# LEDFB.net
KiCad netlist of a schematic drawn in EAGLE
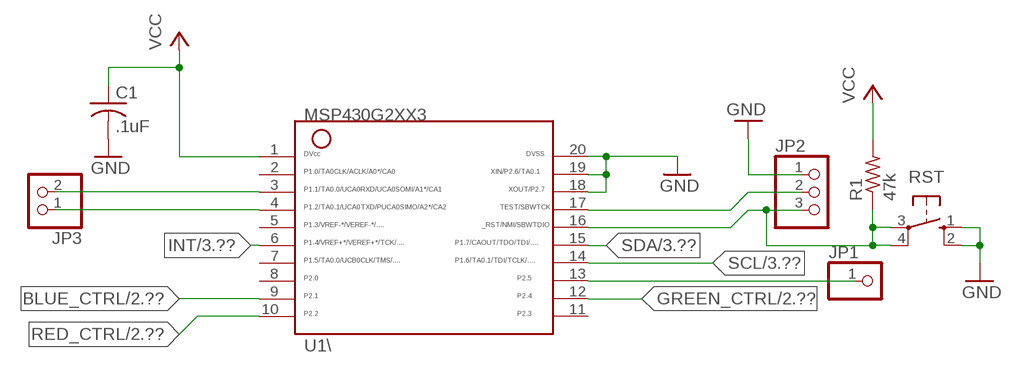
[diagram p0: schematic, sheet 1]
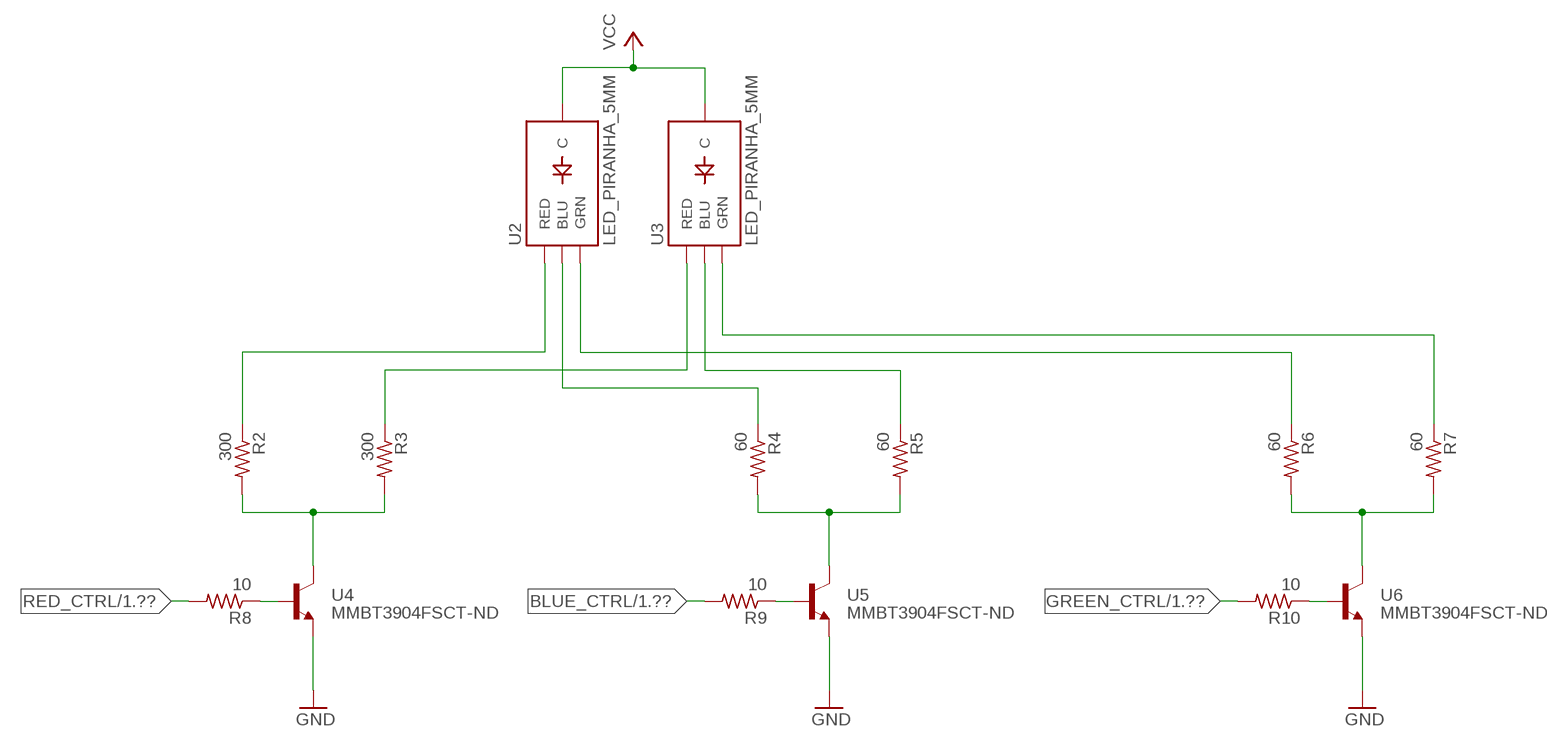
[diagram p1: schematic, sheet 2]
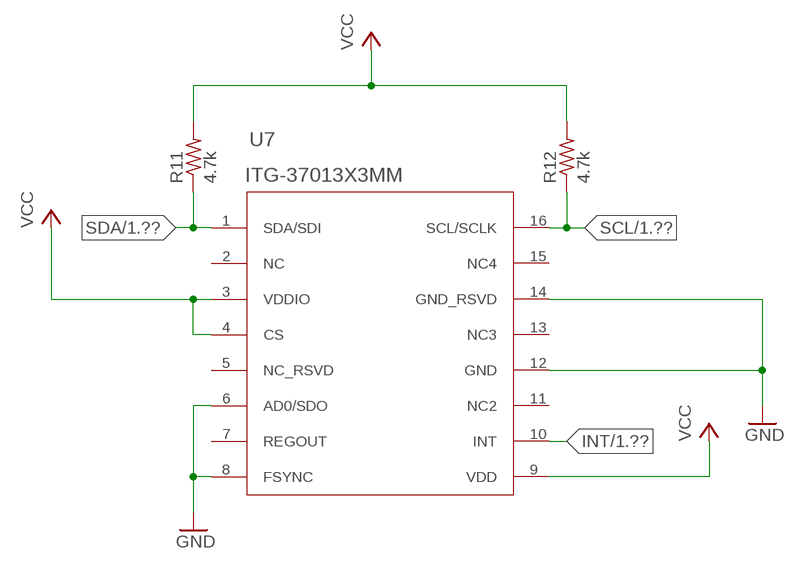
[diagram p2: schematic, sheet 3]
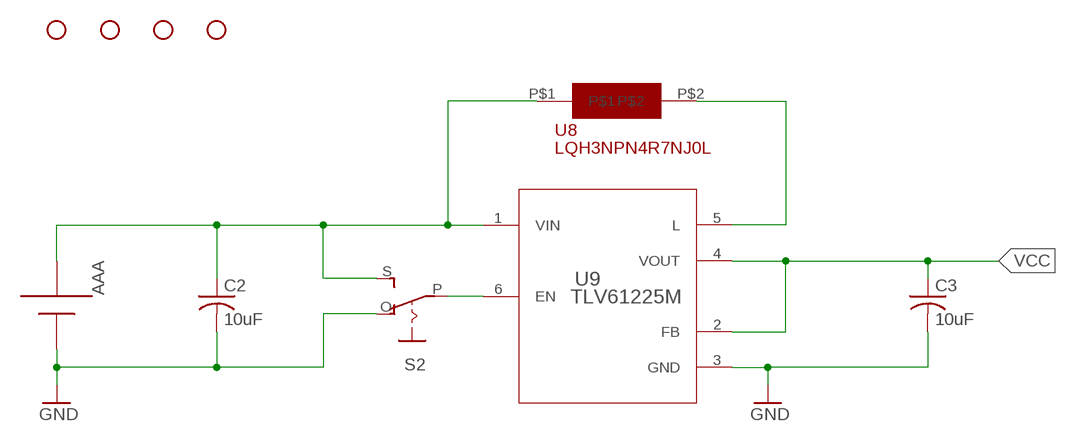
[diagram p3: schematic, sheet 4]

(export (version "E")
  (design (tool "Eeschema 10.0.6"))
  (components
    (comp (ref "C1")
      (value ".1uF")
      (footprint "eagle-import:C0805")
      (libsource (lib "eagle-import") (part "C-USC0805"))
    )
    (comp (ref "JP1")
      (value "PINHD-1X1")
      (footprint "eagle-import:1X01")
      (libsource (lib "eagle-import") (part "PINHD-1X1"))
    )
    (comp (ref "JP2")
      (value "PINHD-1X3")
      (footprint "eagle-import:1X03")
      (libsource (lib "eagle-import") (part "PINHD-1X3"))
    )
    (comp (ref "JP3")
      (value "PINHD-1X2")
      (footprint "eagle-import:1X02")
      (libsource (lib "eagle-import") (part "PINHD-1X2"))
    )
    (comp (ref "R1")
      (value "47k")
      (footprint "eagle-import:R0805")
      (libsource (lib "eagle-import") (part "R-US_R0805"))
    )
    (comp (ref "RST")
      (value "10-XX")
      (footprint "eagle-import:B3F-10XX")
      (fields (field (name "MPN") "B3F-1000"))
      (libsource (lib "eagle-import") (part "10-XX"))
    )
    (comp (ref "U1\\")
      (value "G2XX3---PW20")
      (footprint "eagle-import:PW20")
      (libsource (lib "eagle-import") (part "G2XX3---PW20"))
    )
    (comp (ref "R2")
      (value "300")
      (footprint "eagle-import:R0805")
      (libsource (lib "eagle-import") (part "R-US_R0805"))
    )
    (comp (ref "R3")
      (value "300")
      (footprint "eagle-import:R0805")
      (libsource (lib "eagle-import") (part "R-US_R0805"))
    )
    (comp (ref "R4")
      (value "60")
      (footprint "eagle-import:R0805")
      (libsource (lib "eagle-import") (part "R-US_R0805"))
    )
    (comp (ref "R5")
      (value "60")
      (footprint "eagle-import:R0805")
      (libsource (lib "eagle-import") (part "R-US_R0805"))
    )
    (comp (ref "R6")
      (value "60")
      (footprint "eagle-import:R0805")
      (libsource (lib "eagle-import") (part "R-US_R0805"))
    )
    (comp (ref "R7")
      (value "60")
      (footprint "eagle-import:R0805")
      (libsource (lib "eagle-import") (part "R-US_R0805"))
    )
    (comp (ref "R8")
      (value "10")
      (footprint "eagle-import:R0805")
      (libsource (lib "eagle-import") (part "R-US_R0805"))
    )
    (comp (ref "R9")
      (value "10")
      (footprint "eagle-import:R0805")
      (libsource (lib "eagle-import") (part "R-US_R0805"))
    )
    (comp (ref "R10")
      (value "10")
      (footprint "eagle-import:R0805")
      (libsource (lib "eagle-import") (part "R-US_R0805"))
    )
    (comp (ref "U2")
      (value "LED_PIRANHA_5MM")
      (footprint "eagle-import:LED_PIRANHA_5MM")
      (libsource (lib "eagle-import") (part "LED_PIRANHA_5MM"))
    )
    (comp (ref "U3")
      (value "LED_PIRANHA_5MM")
      (footprint "eagle-import:LED_PIRANHA_5MM")
      (libsource (lib "eagle-import") (part "LED_PIRANHA_5MM"))
    )
    (comp (ref "U4")
      (value "MMBT3904FSCT-ND")
      (footprint "eagle-import:SOT-23")
      (libsource (lib "eagle-import") (part "MMBT3904FSCT-ND"))
    )
    (comp (ref "U5")
      (value "MMBT3904FSCT-ND")
      (footprint "eagle-import:SOT-23")
      (libsource (lib "eagle-import") (part "MMBT3904FSCT-ND"))
    )
    (comp (ref "U6")
      (value "MMBT3904FSCT-ND")
      (footprint "eagle-import:SOT-23")
      (libsource (lib "eagle-import") (part "MMBT3904FSCT-ND"))
    )
    (comp (ref "AAA")
      (value "AAA")
      (footprint "eagle-import:12BH412")
      (libsource (lib "eagle-import") (part "AAA"))
    )
    (comp (ref "C2")
      (value "10uF")
      (footprint "eagle-import:C0805")
      (libsource (lib "eagle-import") (part "C-USC0805"))
    )
    (comp (ref "C3")
      (value "10uF")
      (footprint "eagle-import:C0805")
      (libsource (lib "eagle-import") (part "C-USC0805"))
    )
    (comp (ref "H1")
      (value "STAND-OFF")
      (footprint "eagle-import:STAND-OFF")
      (libsource (lib "eagle-import") (part "STAND-OFF"))
    )
    (comp (ref "H2")
      (value "STAND-OFF")
      (footprint "eagle-import:STAND-OFF")
      (libsource (lib "eagle-import") (part "STAND-OFF"))
    )
    (comp (ref "H3")
      (value "STAND-OFF")
      (footprint "eagle-import:STAND-OFF")
      (libsource (lib "eagle-import") (part "STAND-OFF"))
    )
    (comp (ref "H4")
      (value "STAND-OFF")
      (footprint "eagle-import:STAND-OFF")
      (libsource (lib "eagle-import") (part "STAND-OFF"))
    )
    (comp (ref "S2")
      (value "EG1218S")
      (footprint "eagle-import:EG1218")
      (libsource (lib "eagle-import") (part "EG1218S"))
    )
    (comp (ref "U8")
      (value "LQH3NPN4R7NJ0")
      (footprint "eagle-import:1212")
      (libsource (lib "eagle-import") (part "LQH3NPN4R7NJ0"))
    )
    (comp (ref "U9")
      (value "TLV61225M")
      (footprint "eagle-import:DCK0006A_M")
      (libsource (lib "eagle-import") (part "TLV61225M"))
    )
    (comp (ref "R11")
      (value "4.7k")
      (footprint "eagle-import:M0805")
      (libsource (lib "eagle-import") (part "R-US_M0805"))
    )
    (comp (ref "R12")
      (value "4.7k")
      (footprint "eagle-import:M0805")
      (libsource (lib "eagle-import") (part "R-US_M0805"))
    )
    (comp (ref "U7")
      (value "ITG-37013X3MM")
      (footprint "eagle-import:QFN-16")
      (libsource (lib "eagle-import") (part "ITG-37013X3MM"))
    )
  )
  (nets
    (net (code "1") (name "BLUE_CTRL") (class "Default")
      (node (ref "R9") (pin "2") (pinfunction "2_2") (pintype "passive"))
      (node (ref "U1\\") (pin "9") (pinfunction "9_9") (pintype "bidirectional"))
    )
    (net (code "2") (name "GND") (class "Default")
      (node (ref "AAA") (pin "-") (pinfunction "-_-") (pintype "bidirectional"))
      (node (ref "C1") (pin "2") (pinfunction "2_2") (pintype "passive"))
      (node (ref "C2") (pin "2") (pinfunction "2_2") (pintype "passive"))
      (node (ref "C3") (pin "2") (pinfunction "2_2") (pintype "passive"))
      (node (ref "JP2") (pin "1") (pinfunction "1_1") (pintype "passive"))
      (node (ref "RST") (pin "1") (pinfunction "S_1") (pintype "passive"))
      (node (ref "RST") (pin "2") (pinfunction "S1_2") (pintype "passive"))
      (node (ref "S2") (pin "O") (pinfunction "O_O") (pintype "passive"))
      (node (ref "U1\\") (pin "18") (pinfunction "18_18") (pintype "bidirectional"))
      (node (ref "U1\\") (pin "19") (pinfunction "19_19") (pintype "bidirectional"))
      (node (ref "U1\\") (pin "20") (pinfunction "20_20") (pintype "bidirectional"))
      (node (ref "U4") (pin "2") (pinfunction "E_2") (pintype "passive"))
      (node (ref "U5") (pin "2") (pinfunction "E_2") (pintype "passive"))
      (node (ref "U6") (pin "2") (pinfunction "E_2") (pintype "passive"))
      (node (ref "U7") (pin "12") (pinfunction "GND_12") (pintype "power_in"))
      (node (ref "U7") (pin "14") (pinfunction "GND_RSVD_14") (pintype "power_in"))
      (node (ref "U7") (pin "6") (pinfunction "AD0/SDO_6") (pintype "input"))
      (node (ref "U7") (pin "8") (pinfunction "FSYNC_8") (pintype "passive"))
      (node (ref "U9") (pin "3") (pinfunction "GND_3") (pintype "power_in"))
    )
    (net (code "3") (name "GREEN_CTRL") (class "Default")
      (node (ref "R10") (pin "2") (pinfunction "2_2") (pintype "passive"))
      (node (ref "U1\\") (pin "12") (pinfunction "12_12") (pintype "bidirectional"))
    )
    (net (code "4") (name "INT") (class "Default")
      (node (ref "U1\\") (pin "6") (pinfunction "6_6") (pintype "bidirectional"))
      (node (ref "U7") (pin "10") (pinfunction "INT_10") (pintype "power_in"))
    )
    (net (code "5") (name "NC3") (class "Default")
      (node (ref "U7") (pin "13") (pinfunction "NC3_13") (pintype "power_in"))
    )
    (net (code "6") (name "NC4") (class "Default")
      (node (ref "U7") (pin "15") (pinfunction "NC4_15") (pintype "power_in"))
    )
    (net (code "7") (name "NC_RSVD") (class "Default")
      (node (ref "U7") (pin "5") (pinfunction "NC_RSVD_5") (pintype "power_in"))
    )
    (net (code "8") (name "Net-(JP1-Pad1)") (class "Default")
      (node (ref "JP1") (pin "1") (pinfunction "1_1") (pintype "passive"))
      (node (ref "U1\\") (pin "13") (pinfunction "13_13") (pintype "bidirectional"))
    )
    (net (code "9") (name "Net-(JP2-Pad2)") (class "Default")
      (node (ref "JP2") (pin "2") (pinfunction "2_2") (pintype "passive"))
      (node (ref "U1\\") (pin "17") (pinfunction "17_17") (pintype "bidirectional"))
    )
    (net (code "10") (name "Net-(JP3-Pad1)") (class "Default")
      (node (ref "JP3") (pin "1") (pinfunction "1_1") (pintype "passive"))
      (node (ref "U1\\") (pin "4") (pinfunction "4_4") (pintype "bidirectional"))
    )
    (net (code "11") (name "Net-(JP3-Pad2)") (class "Default")
      (node (ref "JP3") (pin "2") (pinfunction "2_2") (pintype "passive"))
      (node (ref "U1\\") (pin "3") (pinfunction "3_3") (pintype "bidirectional"))
    )
    (net (code "12") (name "Net-(RST-P)") (class "Default")
      (node (ref "JP2") (pin "3") (pinfunction "3_3") (pintype "passive"))
      (node (ref "R1") (pin "1") (pinfunction "1_1") (pintype "passive"))
      (node (ref "RST") (pin "3") (pinfunction "P_3") (pintype "passive"))
      (node (ref "RST") (pin "4") (pinfunction "P1_4") (pintype "passive"))
      (node (ref "U1\\") (pin "16") (pinfunction "16_16") (pintype "bidirectional"))
    )
    (net (code "13") (name "Net-(U2-BLU)") (class "Default")
      (node (ref "R4") (pin "1") (pinfunction "1_1") (pintype "passive"))
      (node (ref "U2") (pin "B") (pinfunction "BLU_B") (pintype "bidirectional"))
    )
    (net (code "14") (name "Net-(U2-GRN)") (class "Default")
      (node (ref "R6") (pin "1") (pinfunction "1_1") (pintype "passive"))
      (node (ref "U2") (pin "G") (pinfunction "GRN_G") (pintype "bidirectional"))
    )
    (net (code "15") (name "Net-(U2-RED)") (class "Default")
      (node (ref "R2") (pin "1") (pinfunction "1_1") (pintype "passive"))
      (node (ref "U2") (pin "R") (pinfunction "RED_R") (pintype "bidirectional"))
    )
    (net (code "16") (name "Net-(U3-BLU)") (class "Default")
      (node (ref "R5") (pin "1") (pinfunction "1_1") (pintype "passive"))
      (node (ref "U3") (pin "B") (pinfunction "BLU_B") (pintype "bidirectional"))
    )
    (net (code "17") (name "Net-(U3-GRN)") (class "Default")
      (node (ref "R7") (pin "1") (pinfunction "1_1") (pintype "passive"))
      (node (ref "U3") (pin "G") (pinfunction "GRN_G") (pintype "bidirectional"))
    )
    (net (code "18") (name "Net-(U3-RED)") (class "Default")
      (node (ref "R3") (pin "1") (pinfunction "1_1") (pintype "passive"))
      (node (ref "U3") (pin "R") (pinfunction "RED_R") (pintype "bidirectional"))
    )
    (net (code "19") (name "Net-(U4-B)") (class "Default")
      (node (ref "R8") (pin "1") (pinfunction "1_1") (pintype "passive"))
      (node (ref "U4") (pin "1") (pinfunction "B_1") (pintype "passive"))
    )
    (net (code "20") (name "Net-(U4-C)") (class "Default")
      (node (ref "R2") (pin "2") (pinfunction "2_2") (pintype "passive"))
      (node (ref "R3") (pin "2") (pinfunction "2_2") (pintype "passive"))
      (node (ref "U4") (pin "3") (pinfunction "C_3") (pintype "passive"))
    )
    (net (code "21") (name "Net-(U5-B)") (class "Default")
      (node (ref "R9") (pin "1") (pinfunction "1_1") (pintype "passive"))
      (node (ref "U5") (pin "1") (pinfunction "B_1") (pintype "passive"))
    )
    (net (code "22") (name "Net-(U5-C)") (class "Default")
      (node (ref "R4") (pin "2") (pinfunction "2_2") (pintype "passive"))
      (node (ref "R5") (pin "2") (pinfunction "2_2") (pintype "passive"))
      (node (ref "U5") (pin "3") (pinfunction "C_3") (pintype "passive"))
    )
    (net (code "23") (name "Net-(U6-B)") (class "Default")
      (node (ref "R10") (pin "1") (pinfunction "1_1") (pintype "passive"))
      (node (ref "U6") (pin "1") (pinfunction "B_1") (pintype "passive"))
    )
    (net (code "24") (name "Net-(U6-C)") (class "Default")
      (node (ref "R6") (pin "2") (pinfunction "2_2") (pintype "passive"))
      (node (ref "R7") (pin "2") (pinfunction "2_2") (pintype "passive"))
      (node (ref "U6") (pin "3") (pinfunction "C_3") (pintype "passive"))
    )
    (net (code "25") (name "Net-(U9-EN)") (class "Default")
      (node (ref "S2") (pin "P") (pinfunction "P_P") (pintype "passive"))
      (node (ref "U9") (pin "6") (pinfunction "EN_6") (pintype "input"))
    )
    (net (code "26") (name "Net-(U9-L)") (class "Default")
      (node (ref "U8") (pin "P$2") (pinfunction "P$2_P$2") (pintype "bidirectional"))
      (node (ref "U9") (pin "5") (pinfunction "L_5") (pintype "input"))
    )
    (net (code "27") (name "Net-(U9-VIN)") (class "Default")
      (node (ref "AAA") (pin "+") (pinfunction "+_+") (pintype "bidirectional"))
      (node (ref "C2") (pin "1") (pinfunction "1_1") (pintype "passive"))
      (node (ref "S2") (pin "S") (pinfunction "S_S") (pintype "passive"))
      (node (ref "U8") (pin "P$1") (pinfunction "P$1_P$1") (pintype "bidirectional"))
      (node (ref "U9") (pin "1") (pinfunction "VIN_1") (pintype "power_in"))
    )
    (net (code "28") (name "RED_CTRL") (class "Default")
      (node (ref "R8") (pin "2") (pinfunction "2_2") (pintype "passive"))
      (node (ref "U1\\") (pin "10") (pinfunction "10_10") (pintype "bidirectional"))
    )
    (net (code "29") (name "SCL") (class "Default")
      (node (ref "R12") (pin "1") (pinfunction "1_1") (pintype "passive"))
      (node (ref "U1\\") (pin "14") (pinfunction "14_14") (pintype "bidirectional"))
      (node (ref "U7") (pin "16") (pinfunction "SCL/SCLK_16") (pintype "input"))
    )
    (net (code "30") (name "SDA") (class "Default")
      (node (ref "R11") (pin "1") (pinfunction "1_1") (pintype "passive"))
      (node (ref "U1\\") (pin "15") (pinfunction "15_15") (pintype "bidirectional"))
      (node (ref "U7") (pin "1") (pinfunction "SDA/SDI_1") (pintype "power_in"))
    )
    (net (code "31") (name "VCC") (class "Default")
      (node (ref "C1") (pin "1") (pinfunction "1_1") (pintype "passive"))
      (node (ref "C3") (pin "1") (pinfunction "1_1") (pintype "passive"))
      (node (ref "R1") (pin "2") (pinfunction "2_2") (pintype "passive"))
      (node (ref "R11") (pin "2") (pinfunction "2_2") (pintype "passive"))
      (node (ref "R12") (pin "2") (pinfunction "2_2") (pintype "passive"))
      (node (ref "U1\\") (pin "1") (pinfunction "1_1") (pintype "bidirectional"))
      (node (ref "U2") (pin "C") (pinfunction "C_C") (pintype "bidirectional"))
      (node (ref "U3") (pin "C") (pinfunction "C_C") (pintype "bidirectional"))
      (node (ref "U7") (pin "3") (pinfunction "VDDIO_3") (pintype "power_in"))
      (node (ref "U7") (pin "4") (pinfunction "CS_4") (pintype "power_in"))
      (node (ref "U7") (pin "9") (pinfunction "VDD_9") (pintype "power_in"))
      (node (ref "U9") (pin "2") (pinfunction "FB_2") (pintype "input"))
      (node (ref "U9") (pin "4") (pinfunction "VOUT_4") (pintype "power_in"))
    )
    (net (code "32") (name "unconnected-(U1\\-Pad2)") (class "Default")
      (node (ref "U1\\") (pin "2") (pinfunction "2_2") (pintype "bidirectional"))
    )
    (net (code "33") (name "unconnected-(U1\\-Pad5)") (class "Default")
      (node (ref "U1\\") (pin "5") (pinfunction "5_5") (pintype "bidirectional"))
    )
    (net (code "34") (name "unconnected-(U1\\-Pad7)") (class "Default")
      (node (ref "U1\\") (pin "7") (pinfunction "7_7") (pintype "bidirectional"))
    )
    (net (code "35") (name "unconnected-(U1\\-Pad8)") (class "Default")
      (node (ref "U1\\") (pin "8") (pinfunction "8_8") (pintype "bidirectional"))
    )
    (net (code "36") (name "unconnected-(U1\\-Pad11)") (class "Default")
      (node (ref "U1\\") (pin "11") (pinfunction "11_11") (pintype "bidirectional"))
    )
    (net (code "37") (name "unconnected-(U7-NC-Pad2)") (class "Default")
      (node (ref "U7") (pin "2") (pinfunction "NC_2") (pintype "open_collector"))
    )
    (net (code "38") (name "unconnected-(U7-NC2-Pad11)") (class "Default")
      (node (ref "U7") (pin "11") (pinfunction "NC2_11") (pintype "input"))
    )
    (net (code "39") (name "unconnected-(U7-REGOUT-Pad7)") (class "Default")
      (node (ref "U7") (pin "7") (pinfunction "REGOUT_7") (pintype "input"))
    )
  )
)
